# DiyMKbd.net
KiCad netlist of a schematic drawn in EAGLE
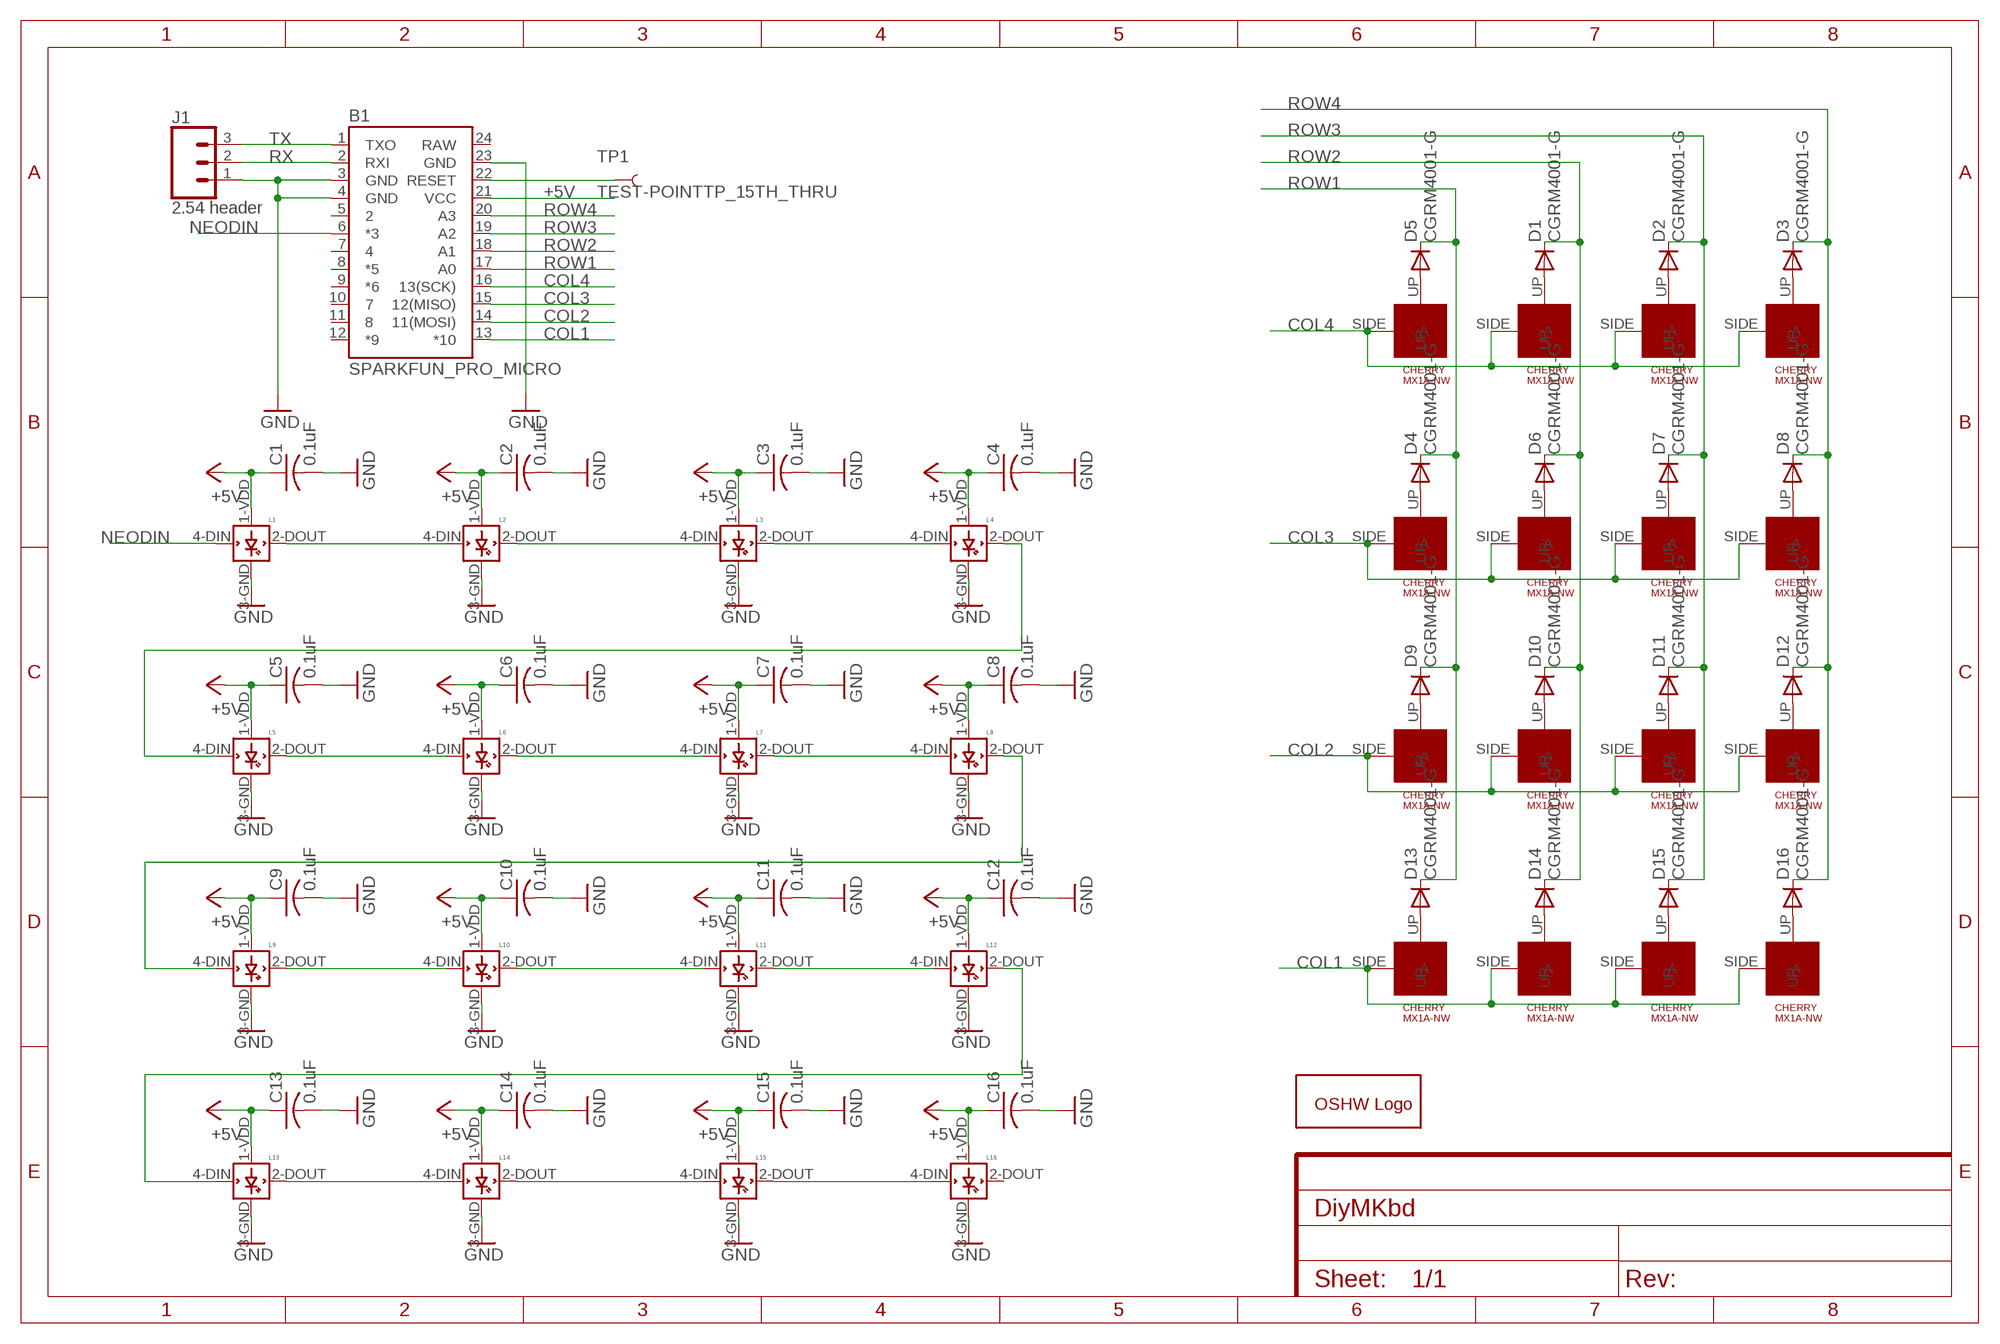
[diagram p0: schematic, sheet 1]

(export (version "E")
  (design (tool "Eeschema 10.0.6"))
  (components
    (comp (ref "B1")
      (value "SPARKFUN_PRO_MICRO")
      (footprint "eagle-import:SPARKFUN_PRO_MICRO")
      (libsource (lib "eagle-import") (part "SPARKFUN_PRO_MICRO"))
    )
    (comp (ref "C1")
      (value "0.1uF")
      (footprint "eagle-import:C0603")
      (libsource (lib "eagle-import") (part "C-USC0603"))
    )
    (comp (ref "C2")
      (value "0.1uF")
      (footprint "eagle-import:C0603")
      (libsource (lib "eagle-import") (part "C-USC0603"))
    )
    (comp (ref "C3")
      (value "0.1uF")
      (footprint "eagle-import:C0603")
      (libsource (lib "eagle-import") (part "C-USC0603"))
    )
    (comp (ref "C4")
      (value "0.1uF")
      (footprint "eagle-import:C0603")
      (libsource (lib "eagle-import") (part "C-USC0603"))
    )
    (comp (ref "C5")
      (value "0.1uF")
      (footprint "eagle-import:C0603")
      (libsource (lib "eagle-import") (part "C-USC0603"))
    )
    (comp (ref "C6")
      (value "0.1uF")
      (footprint "eagle-import:C0603")
      (libsource (lib "eagle-import") (part "C-USC0603"))
    )
    (comp (ref "C7")
      (value "0.1uF")
      (footprint "eagle-import:C0603")
      (libsource (lib "eagle-import") (part "C-USC0603"))
    )
    (comp (ref "C8")
      (value "0.1uF")
      (footprint "eagle-import:C0603")
      (libsource (lib "eagle-import") (part "C-USC0603"))
    )
    (comp (ref "C9")
      (value "0.1uF")
      (footprint "eagle-import:C0603")
      (libsource (lib "eagle-import") (part "C-USC0603"))
    )
    (comp (ref "C10")
      (value "0.1uF")
      (footprint "eagle-import:C0603")
      (libsource (lib "eagle-import") (part "C-USC0603"))
    )
    (comp (ref "C11")
      (value "0.1uF")
      (footprint "eagle-import:C0603")
      (libsource (lib "eagle-import") (part "C-USC0603"))
    )
    (comp (ref "C12")
      (value "0.1uF")
      (footprint "eagle-import:C0603")
      (libsource (lib "eagle-import") (part "C-USC0603"))
    )
    (comp (ref "C13")
      (value "0.1uF")
      (footprint "eagle-import:C0603")
      (libsource (lib "eagle-import") (part "C-USC0603"))
    )
    (comp (ref "C14")
      (value "0.1uF")
      (footprint "eagle-import:C0603")
      (libsource (lib "eagle-import") (part "C-USC0603"))
    )
    (comp (ref "C15")
      (value "0.1uF")
      (footprint "eagle-import:C0603")
      (libsource (lib "eagle-import") (part "C-USC0603"))
    )
    (comp (ref "C16")
      (value "0.1uF")
      (footprint "eagle-import:C0603")
      (libsource (lib "eagle-import") (part "C-USC0603"))
    )
    (comp (ref "D1")
      (value "CGRM4001-G")
      (footprint "eagle-import:SOD-123_MINI-SMA")
      (libsource (lib "eagle-import") (part "CGRM400-G1"))
    )
    (comp (ref "D2")
      (value "CGRM4001-G")
      (footprint "eagle-import:SOD-123_MINI-SMA")
      (libsource (lib "eagle-import") (part "CGRM400-G1"))
    )
    (comp (ref "D3")
      (value "CGRM4001-G")
      (footprint "eagle-import:SOD-123_MINI-SMA")
      (libsource (lib "eagle-import") (part "CGRM400-G1"))
    )
    (comp (ref "D4")
      (value "CGRM4001-G")
      (footprint "eagle-import:SOD-123_MINI-SMA")
      (libsource (lib "eagle-import") (part "CGRM400-G1"))
    )
    (comp (ref "D5")
      (value "CGRM4001-G")
      (footprint "eagle-import:SOD-123_MINI-SMA")
      (libsource (lib "eagle-import") (part "CGRM400-G1"))
    )
    (comp (ref "D6")
      (value "CGRM4001-G")
      (footprint "eagle-import:SOD-123_MINI-SMA")
      (libsource (lib "eagle-import") (part "CGRM400-G1"))
    )
    (comp (ref "D7")
      (value "CGRM4001-G")
      (footprint "eagle-import:SOD-123_MINI-SMA")
      (libsource (lib "eagle-import") (part "CGRM400-G1"))
    )
    (comp (ref "D8")
      (value "CGRM4001-G")
      (footprint "eagle-import:SOD-123_MINI-SMA")
      (libsource (lib "eagle-import") (part "CGRM400-G1"))
    )
    (comp (ref "D9")
      (value "CGRM4001-G")
      (footprint "eagle-import:SOD-123_MINI-SMA")
      (libsource (lib "eagle-import") (part "CGRM400-G1"))
    )
    (comp (ref "D10")
      (value "CGRM4001-G")
      (footprint "eagle-import:SOD-123_MINI-SMA")
      (libsource (lib "eagle-import") (part "CGRM400-G1"))
    )
    (comp (ref "D11")
      (value "CGRM4001-G")
      (footprint "eagle-import:SOD-123_MINI-SMA")
      (libsource (lib "eagle-import") (part "CGRM400-G1"))
    )
    (comp (ref "D12")
      (value "CGRM4001-G")
      (footprint "eagle-import:SOD-123_MINI-SMA")
      (libsource (lib "eagle-import") (part "CGRM400-G1"))
    )
    (comp (ref "D13")
      (value "CGRM4001-G")
      (footprint "eagle-import:SOD-123_MINI-SMA")
      (libsource (lib "eagle-import") (part "CGRM400-G1"))
    )
    (comp (ref "D14")
      (value "CGRM4001-G")
      (footprint "eagle-import:SOD-123_MINI-SMA")
      (libsource (lib "eagle-import") (part "CGRM400-G1"))
    )
    (comp (ref "D15")
      (value "CGRM4001-G")
      (footprint "eagle-import:SOD-123_MINI-SMA")
      (libsource (lib "eagle-import") (part "CGRM400-G1"))
    )
    (comp (ref "D16")
      (value "CGRM4001-G")
      (footprint "eagle-import:SOD-123_MINI-SMA")
      (libsource (lib "eagle-import") (part "CGRM400-G1"))
    )
    (comp (ref "GOLD_ORB_SM1")
      (value "OSHWLOGOLOGO5MM")
      (footprint "eagle-import:OSHW_5MM")
      (libsource (lib "eagle-import") (part "OSHWLOGOLOGO5MM"))
    )
    (comp (ref "J1")
      (value "2.54 header")
      (footprint "eagle-import:1X03_LOCK")
      (libsource (lib "eagle-import") (part "CONN_03LOCK"))
    )
    (comp (ref "L1")
      (value "WS2812B")
      (footprint "eagle-import:WS2812B")
      (libsource (lib "eagle-import") (part "WS2812B"))
    )
    (comp (ref "L2")
      (value "WS2812B")
      (footprint "eagle-import:WS2812B")
      (libsource (lib "eagle-import") (part "WS2812B"))
    )
    (comp (ref "L3")
      (value "WS2812B")
      (footprint "eagle-import:WS2812B")
      (libsource (lib "eagle-import") (part "WS2812B"))
    )
    (comp (ref "L4")
      (value "WS2812B")
      (footprint "eagle-import:WS2812B")
      (libsource (lib "eagle-import") (part "WS2812B"))
    )
    (comp (ref "L5")
      (value "WS2812B")
      (footprint "eagle-import:WS2812B")
      (libsource (lib "eagle-import") (part "WS2812B"))
    )
    (comp (ref "L6")
      (value "WS2812B")
      (footprint "eagle-import:WS2812B")
      (libsource (lib "eagle-import") (part "WS2812B"))
    )
    (comp (ref "L7")
      (value "WS2812B")
      (footprint "eagle-import:WS2812B")
      (libsource (lib "eagle-import") (part "WS2812B"))
    )
    (comp (ref "L8")
      (value "WS2812B")
      (footprint "eagle-import:WS2812B")
      (libsource (lib "eagle-import") (part "WS2812B"))
    )
    (comp (ref "L9")
      (value "WS2812B")
      (footprint "eagle-import:WS2812B")
      (libsource (lib "eagle-import") (part "WS2812B"))
    )
    (comp (ref "L10")
      (value "WS2812B")
      (footprint "eagle-import:WS2812B")
      (libsource (lib "eagle-import") (part "WS2812B"))
    )
    (comp (ref "L11")
      (value "WS2812B")
      (footprint "eagle-import:WS2812B")
      (libsource (lib "eagle-import") (part "WS2812B"))
    )
    (comp (ref "L12")
      (value "WS2812B")
      (footprint "eagle-import:WS2812B")
      (libsource (lib "eagle-import") (part "WS2812B"))
    )
    (comp (ref "L13")
      (value "WS2812B")
      (footprint "eagle-import:WS2812B")
      (libsource (lib "eagle-import") (part "WS2812B"))
    )
    (comp (ref "L14")
      (value "WS2812B")
      (footprint "eagle-import:WS2812B")
      (libsource (lib "eagle-import") (part "WS2812B"))
    )
    (comp (ref "L15")
      (value "WS2812B")
      (footprint "eagle-import:WS2812B")
      (libsource (lib "eagle-import") (part "WS2812B"))
    )
    (comp (ref "L16")
      (value "WS2812B")
      (footprint "eagle-import:WS2812B")
      (libsource (lib "eagle-import") (part "WS2812B"))
    )
    (comp (ref "TP1")
      (value "TEST-POINTTP_15TH_THRU")
      (footprint "eagle-import:TP_15TH")
      (libsource (lib "eagle-import") (part "TEST-POINTTP_15TH_THRU"))
    )
    (comp (ref "U$1")
      (value "CHERRY-MX1A-E1NW")
      (footprint "eagle-import:CHERRYMX-NN")
      (libsource (lib "eagle-import") (part "CHERRY-MX1A-E1NW"))
    )
    (comp (ref "U$2")
      (value "CHERRY-MX1A-E1NW")
      (footprint "eagle-import:CHERRYMX-NN")
      (libsource (lib "eagle-import") (part "CHERRY-MX1A-E1NW"))
    )
    (comp (ref "U$3")
      (value "CHERRY-MX1A-E1NW")
      (footprint "eagle-import:CHERRYMX-NN")
      (libsource (lib "eagle-import") (part "CHERRY-MX1A-E1NW"))
    )
    (comp (ref "U$4")
      (value "CHERRY-MX1A-E1NW")
      (footprint "eagle-import:CHERRYMX-NN")
      (libsource (lib "eagle-import") (part "CHERRY-MX1A-E1NW"))
    )
    (comp (ref "U$7")
      (value "CHERRY-MX1A-E1NW")
      (footprint "eagle-import:CHERRYMX-NN")
      (libsource (lib "eagle-import") (part "CHERRY-MX1A-E1NW"))
    )
    (comp (ref "U$8")
      (value "CHERRY-MX1A-E1NW")
      (footprint "eagle-import:CHERRYMX-NN")
      (libsource (lib "eagle-import") (part "CHERRY-MX1A-E1NW"))
    )
    (comp (ref "U$9")
      (value "CHERRY-MX1A-E1NW")
      (footprint "eagle-import:CHERRYMX-NN")
      (libsource (lib "eagle-import") (part "CHERRY-MX1A-E1NW"))
    )
    (comp (ref "U$10")
      (value "CHERRY-MX1A-E1NW")
      (footprint "eagle-import:CHERRYMX-NN")
      (libsource (lib "eagle-import") (part "CHERRY-MX1A-E1NW"))
    )
    (comp (ref "U$19")
      (value "CHERRY-MX1A-E1NW")
      (footprint "eagle-import:CHERRYMX-NN")
      (libsource (lib "eagle-import") (part "CHERRY-MX1A-E1NW"))
    )
    (comp (ref "U$20")
      (value "CHERRY-MX1A-E1NW")
      (footprint "eagle-import:CHERRYMX-NN")
      (libsource (lib "eagle-import") (part "CHERRY-MX1A-E1NW"))
    )
    (comp (ref "U$21")
      (value "CHERRY-MX1A-E1NW")
      (footprint "eagle-import:CHERRYMX-NN")
      (libsource (lib "eagle-import") (part "CHERRY-MX1A-E1NW"))
    )
    (comp (ref "U$22")
      (value "CHERRY-MX1A-E1NW")
      (footprint "eagle-import:CHERRYMX-NN")
      (libsource (lib "eagle-import") (part "CHERRY-MX1A-E1NW"))
    )
    (comp (ref "U$25")
      (value "CHERRY-MX1A-E1NW")
      (footprint "eagle-import:CHERRYMX-NN")
      (libsource (lib "eagle-import") (part "CHERRY-MX1A-E1NW"))
    )
    (comp (ref "U$26")
      (value "CHERRY-MX1A-E1NW")
      (footprint "eagle-import:CHERRYMX-NN")
      (libsource (lib "eagle-import") (part "CHERRY-MX1A-E1NW"))
    )
    (comp (ref "U$27")
      (value "CHERRY-MX1A-E1NW")
      (footprint "eagle-import:CHERRYMX-NN")
      (libsource (lib "eagle-import") (part "CHERRY-MX1A-E1NW"))
    )
    (comp (ref "U$28")
      (value "CHERRY-MX1A-E1NW")
      (footprint "eagle-import:CHERRYMX-NN")
      (libsource (lib "eagle-import") (part "CHERRY-MX1A-E1NW"))
    )
  )
  (nets
    (net (code "1") (name "+5V") (class "Default")
      (node (ref "B1") (pin "21") (pinfunction "VCC_21") (pintype "power_in"))
      (node (ref "C1") (pin "1") (pinfunction "1_1") (pintype "passive"))
      (node (ref "C10") (pin "1") (pinfunction "1_1") (pintype "passive"))
      (node (ref "C11") (pin "1") (pinfunction "1_1") (pintype "passive"))
      (node (ref "C12") (pin "1") (pinfunction "1_1") (pintype "passive"))
      (node (ref "C13") (pin "1") (pinfunction "1_1") (pintype "passive"))
      (node (ref "C14") (pin "1") (pinfunction "1_1") (pintype "passive"))
      (node (ref "C15") (pin "1") (pinfunction "1_1") (pintype "passive"))
      (node (ref "C16") (pin "1") (pinfunction "1_1") (pintype "passive"))
      (node (ref "C2") (pin "1") (pinfunction "1_1") (pintype "passive"))
      (node (ref "C3") (pin "1") (pinfunction "1_1") (pintype "passive"))
      (node (ref "C4") (pin "1") (pinfunction "1_1") (pintype "passive"))
      (node (ref "C5") (pin "1") (pinfunction "1_1") (pintype "passive"))
      (node (ref "C6") (pin "1") (pinfunction "1_1") (pintype "passive"))
      (node (ref "C7") (pin "1") (pinfunction "1_1") (pintype "passive"))
      (node (ref "C8") (pin "1") (pinfunction "1_1") (pintype "passive"))
      (node (ref "C9") (pin "1") (pinfunction "1_1") (pintype "passive"))
      (node (ref "L1") (pin "1-VDD") (pinfunction "VDD_1-VDD") (pintype "bidirectional"))
      (node (ref "L10") (pin "1-VDD") (pinfunction "VDD_1-VDD") (pintype "bidirectional"))
      (node (ref "L11") (pin "1-VDD") (pinfunction "VDD_1-VDD") (pintype "bidirectional"))
      (node (ref "L12") (pin "1-VDD") (pinfunction "VDD_1-VDD") (pintype "bidirectional"))
      (node (ref "L13") (pin "1-VDD") (pinfunction "VDD_1-VDD") (pintype "bidirectional"))
      (node (ref "L14") (pin "1-VDD") (pinfunction "VDD_1-VDD") (pintype "bidirectional"))
      (node (ref "L15") (pin "1-VDD") (pinfunction "VDD_1-VDD") (pintype "bidirectional"))
      (node (ref "L16") (pin "1-VDD") (pinfunction "VDD_1-VDD") (pintype "bidirectional"))
      (node (ref "L2") (pin "1-VDD") (pinfunction "VDD_1-VDD") (pintype "bidirectional"))
      (node (ref "L3") (pin "1-VDD") (pinfunction "VDD_1-VDD") (pintype "bidirectional"))
      (node (ref "L4") (pin "1-VDD") (pinfunction "VDD_1-VDD") (pintype "bidirectional"))
      (node (ref "L5") (pin "1-VDD") (pinfunction "VDD_1-VDD") (pintype "bidirectional"))
      (node (ref "L6") (pin "1-VDD") (pinfunction "VDD_1-VDD") (pintype "bidirectional"))
      (node (ref "L7") (pin "1-VDD") (pinfunction "VDD_1-VDD") (pintype "bidirectional"))
      (node (ref "L8") (pin "1-VDD") (pinfunction "VDD_1-VDD") (pintype "bidirectional"))
      (node (ref "L9") (pin "1-VDD") (pinfunction "VDD_1-VDD") (pintype "bidirectional"))
    )
    (net (code "2") (name "/COL1") (class "Default")
      (node (ref "B1") (pin "13") (pinfunction "*10_13") (pintype "bidirectional"))
      (node (ref "U$25") (pin "SIDE") (pinfunction "A_SIDE") (pintype "bidirectional"))
      (node (ref "U$26") (pin "SIDE") (pinfunction "A_SIDE") (pintype "bidirectional"))
      (node (ref "U$27") (pin "SIDE") (pinfunction "A_SIDE") (pintype "bidirectional"))
      (node (ref "U$28") (pin "SIDE") (pinfunction "A_SIDE") (pintype "bidirectional"))
    )
    (net (code "3") (name "/COL2") (class "Default")
      (node (ref "B1") (pin "14") (pinfunction "11(MOSI)_14") (pintype "bidirectional"))
      (node (ref "U$10") (pin "SIDE") (pinfunction "A_SIDE") (pintype "bidirectional"))
      (node (ref "U$7") (pin "SIDE") (pinfunction "A_SIDE") (pintype "bidirectional"))
      (node (ref "U$8") (pin "SIDE") (pinfunction "A_SIDE") (pintype "bidirectional"))
      (node (ref "U$9") (pin "SIDE") (pinfunction "A_SIDE") (pintype "bidirectional"))
    )
    (net (code "4") (name "/COL3") (class "Default")
      (node (ref "B1") (pin "15") (pinfunction "12(MISO)_15") (pintype "bidirectional"))
      (node (ref "U$1") (pin "SIDE") (pinfunction "A_SIDE") (pintype "bidirectional"))
      (node (ref "U$2") (pin "SIDE") (pinfunction "A_SIDE") (pintype "bidirectional"))
      (node (ref "U$3") (pin "SIDE") (pinfunction "A_SIDE") (pintype "bidirectional"))
      (node (ref "U$4") (pin "SIDE") (pinfunction "A_SIDE") (pintype "bidirectional"))
    )
    (net (code "5") (name "/COL4") (class "Default")
      (node (ref "B1") (pin "16") (pinfunction "13(SCK)_16") (pintype "bidirectional"))
      (node (ref "U$19") (pin "SIDE") (pinfunction "A_SIDE") (pintype "bidirectional"))
      (node (ref "U$20") (pin "SIDE") (pinfunction "A_SIDE") (pintype "bidirectional"))
      (node (ref "U$21") (pin "SIDE") (pinfunction "A_SIDE") (pintype "bidirectional"))
      (node (ref "U$22") (pin "SIDE") (pinfunction "A_SIDE") (pintype "bidirectional"))
    )
    (net (code "6") (name "/NEODIN") (class "Default")
      (node (ref "B1") (pin "6") (pinfunction "*3_6") (pintype "bidirectional"))
      (node (ref "L1") (pin "4-DIN") (pinfunction "DIN_4-DIN") (pintype "input"))
    )
    (net (code "7") (name "/RAW") (class "Default")
      (node (ref "B1") (pin "24") (pinfunction "RAW_24") (pintype "power_in"))
    )
    (net (code "8") (name "/ROW1") (class "Default")
      (node (ref "B1") (pin "17") (pinfunction "A0_17") (pintype "bidirectional"))
      (node (ref "D13") (pin "C") (pinfunction "C_C") (pintype "passive"))
      (node (ref "D4") (pin "C") (pinfunction "C_C") (pintype "passive"))
      (node (ref "D5") (pin "C") (pinfunction "C_C") (pintype "passive"))
      (node (ref "D9") (pin "C") (pinfunction "C_C") (pintype "passive"))
    )
    (net (code "9") (name "/ROW2") (class "Default")
      (node (ref "B1") (pin "18") (pinfunction "A1_18") (pintype "bidirectional"))
      (node (ref "D1") (pin "C") (pinfunction "C_C") (pintype "passive"))
      (node (ref "D10") (pin "C") (pinfunction "C_C") (pintype "passive"))
      (node (ref "D14") (pin "C") (pinfunction "C_C") (pintype "passive"))
      (node (ref "D6") (pin "C") (pinfunction "C_C") (pintype "passive"))
    )
    (net (code "10") (name "/ROW3") (class "Default")
      (node (ref "B1") (pin "19") (pinfunction "A2_19") (pintype "bidirectional"))
      (node (ref "D11") (pin "C") (pinfunction "C_C") (pintype "passive"))
      (node (ref "D15") (pin "C") (pinfunction "C_C") (pintype "passive"))
      (node (ref "D2") (pin "C") (pinfunction "C_C") (pintype "passive"))
      (node (ref "D7") (pin "C") (pinfunction "C_C") (pintype "passive"))
    )
    (net (code "11") (name "/ROW4") (class "Default")
      (node (ref "B1") (pin "20") (pinfunction "A3_20") (pintype "bidirectional"))
      (node (ref "D12") (pin "C") (pinfunction "C_C") (pintype "passive"))
      (node (ref "D16") (pin "C") (pinfunction "C_C") (pintype "passive"))
      (node (ref "D3") (pin "C") (pinfunction "C_C") (pintype "passive"))
      (node (ref "D8") (pin "C") (pinfunction "C_C") (pintype "passive"))
    )
    (net (code "12") (name "/RX") (class "Default")
      (node (ref "B1") (pin "2") (pinfunction "RXI_2") (pintype "bidirectional"))
      (node (ref "J1") (pin "2") (pinfunction "2_2") (pintype "passive"))
    )
    (net (code "13") (name "/TX") (class "Default")
      (node (ref "B1") (pin "1") (pinfunction "TXO_1") (pintype "bidirectional"))
      (node (ref "J1") (pin "3") (pinfunction "3_3") (pintype "passive"))
    )
    (net (code "14") (name "GND") (class "Default")
      (node (ref "B1") (pin "23") (pinfunction "GND_23") (pintype "power_in"))
      (node (ref "B1") (pin "3") (pinfunction "GND_3") (pintype "power_in"))
      (node (ref "B1") (pin "4") (pinfunction "GND_4") (pintype "power_in"))
      (node (ref "C1") (pin "2") (pinfunction "2_2") (pintype "passive"))
      (node (ref "C10") (pin "2") (pinfunction "2_2") (pintype "passive"))
      (node (ref "C11") (pin "2") (pinfunction "2_2") (pintype "passive"))
      (node (ref "C12") (pin "2") (pinfunction "2_2") (pintype "passive"))
      (node (ref "C13") (pin "2") (pinfunction "2_2") (pintype "passive"))
      (node (ref "C14") (pin "2") (pinfunction "2_2") (pintype "passive"))
      (node (ref "C15") (pin "2") (pinfunction "2_2") (pintype "passive"))
      (node (ref "C16") (pin "2") (pinfunction "2_2") (pintype "passive"))
      (node (ref "C2") (pin "2") (pinfunction "2_2") (pintype "passive"))
      (node (ref "C3") (pin "2") (pinfunction "2_2") (pintype "passive"))
      (node (ref "C4") (pin "2") (pinfunction "2_2") (pintype "passive"))
      (node (ref "C5") (pin "2") (pinfunction "2_2") (pintype "passive"))
      (node (ref "C6") (pin "2") (pinfunction "2_2") (pintype "passive"))
      (node (ref "C7") (pin "2") (pinfunction "2_2") (pintype "passive"))
      (node (ref "C8") (pin "2") (pinfunction "2_2") (pintype "passive"))
      (node (ref "C9") (pin "2") (pinfunction "2_2") (pintype "passive"))
      (node (ref "J1") (pin "1") (pinfunction "1_1") (pintype "passive"))
      (node (ref "L1") (pin "3-GND") (pinfunction "GND_3-GND") (pintype "bidirectional"))
      (node (ref "L10") (pin "3-GND") (pinfunction "GND_3-GND") (pintype "bidirectional"))
      (node (ref "L11") (pin "3-GND") (pinfunction "GND_3-GND") (pintype "bidirectional"))
      (node (ref "L12") (pin "3-GND") (pinfunction "GND_3-GND") (pintype "bidirectional"))
      (node (ref "L13") (pin "3-GND") (pinfunction "GND_3-GND") (pintype "bidirectional"))
      (node (ref "L14") (pin "3-GND") (pinfunction "GND_3-GND") (pintype "bidirectional"))
      (node (ref "L15") (pin "3-GND") (pinfunction "GND_3-GND") (pintype "bidirectional"))
      (node (ref "L16") (pin "3-GND") (pinfunction "GND_3-GND") (pintype "bidirectional"))
      (node (ref "L2") (pin "3-GND") (pinfunction "GND_3-GND") (pintype "bidirectional"))
      (node (ref "L3") (pin "3-GND") (pinfunction "GND_3-GND") (pintype "bidirectional"))
      (node (ref "L4") (pin "3-GND") (pinfunction "GND_3-GND") (pintype "bidirectional"))
      (node (ref "L5") (pin "3-GND") (pinfunction "GND_3-GND") (pintype "bidirectional"))
      (node (ref "L6") (pin "3-GND") (pinfunction "GND_3-GND") (pintype "bidirectional"))
      (node (ref "L7") (pin "3-GND") (pinfunction "GND_3-GND") (pintype "bidirectional"))
      (node (ref "L8") (pin "3-GND") (pinfunction "GND_3-GND") (pintype "bidirectional"))
      (node (ref "L9") (pin "3-GND") (pinfunction "GND_3-GND") (pintype "bidirectional"))
    )
    (net (code "15") (name "Net-(B1-RESET)") (class "Default")
      (node (ref "B1") (pin "22") (pinfunction "RESET_22") (pintype "bidirectional"))
      (node (ref "TP1") (pin "P$1") (pinfunction "1_P$1") (pintype "bidirectional"))
    )
    (net (code "16") (name "Net-(D1-PadA)") (class "Default")
      (node (ref "D1") (pin "A") (pinfunction "A_A") (pintype "passive"))
      (node (ref "U$20") (pin "UP") (pinfunction "UP_UP") (pintype "bidirectional"))
    )
    (net (code "17") (name "Net-(D2-PadA)") (class "Default")
      (node (ref "D2") (pin "A") (pinfunction "A_A") (pintype "passive"))
      (node (ref "U$21") (pin "UP") (pinfunction "UP_UP") (pintype "bidirectional"))
    )
    (net (code "18") (name "Net-(D3-PadA)") (class "Default")
      (node (ref "D3") (pin "A") (pinfunction "A_A") (pintype "passive"))
      (node (ref "U$22") (pin "UP") (pinfunction "UP_UP") (pintype "bidirectional"))
    )
    (net (code "19") (name "Net-(D4-PadA)") (class "Default")
      (node (ref "D4") (pin "A") (pinfunction "A_A") (pintype "passive"))
      (node (ref "U$2") (pin "UP") (pinfunction "UP_UP") (pintype "bidirectional"))
    )
    (net (code "20") (name "Net-(D5-PadA)") (class "Default")
      (node (ref "D5") (pin "A") (pinfunction "A_A") (pintype "passive"))
      (node (ref "U$19") (pin "UP") (pinfunction "UP_UP") (pintype "bidirectional"))
    )
    (net (code "21") (name "Net-(D6-PadA)") (class "Default")
      (node (ref "D6") (pin "A") (pinfunction "A_A") (pintype "passive"))
      (node (ref "U$1") (pin "UP") (pinfunction "UP_UP") (pintype "bidirectional"))
    )
    (net (code "22") (name "Net-(D7-PadA)") (class "Default")
      (node (ref "D7") (pin "A") (pinfunction "A_A") (pintype "passive"))
      (node (ref "U$3") (pin "UP") (pinfunction "UP_UP") (pintype "bidirectional"))
    )
    (net (code "23") (name "Net-(D8-PadA)") (class "Default")
      (node (ref "D8") (pin "A") (pinfunction "A_A") (pintype "passive"))
      (node (ref "U$4") (pin "UP") (pinfunction "UP_UP") (pintype "bidirectional"))
    )
    (net (code "24") (name "Net-(D9-PadA)") (class "Default")
      (node (ref "D9") (pin "A") (pinfunction "A_A") (pintype "passive"))
      (node (ref "U$7") (pin "UP") (pinfunction "UP_UP") (pintype "bidirectional"))
    )
    (net (code "25") (name "Net-(D10-PadA)") (class "Default")
      (node (ref "D10") (pin "A") (pinfunction "A_A") (pintype "passive"))
      (node (ref "U$8") (pin "UP") (pinfunction "UP_UP") (pintype "bidirectional"))
    )
    (net (code "26") (name "Net-(D11-PadA)") (class "Default")
      (node (ref "D11") (pin "A") (pinfunction "A_A") (pintype "passive"))
      (node (ref "U$9") (pin "UP") (pinfunction "UP_UP") (pintype "bidirectional"))
    )
    (net (code "27") (name "Net-(D12-PadA)") (class "Default")
      (node (ref "D12") (pin "A") (pinfunction "A_A") (pintype "passive"))
      (node (ref "U$10") (pin "UP") (pinfunction "UP_UP") (pintype "bidirectional"))
    )
    (net (code "28") (name "Net-(D13-PadA)") (class "Default")
      (node (ref "D13") (pin "A") (pinfunction "A_A") (pintype "passive"))
      (node (ref "U$25") (pin "UP") (pinfunction "UP_UP") (pintype "bidirectional"))
    )
    (net (code "29") (name "Net-(D14-PadA)") (class "Default")
      (node (ref "D14") (pin "A") (pinfunction "A_A") (pintype "passive"))
      (node (ref "U$26") (pin "UP") (pinfunction "UP_UP") (pintype "bidirectional"))
    )
    (net (code "30") (name "Net-(D15-PadA)") (class "Default")
      (node (ref "D15") (pin "A") (pinfunction "A_A") (pintype "passive"))
      (node (ref "U$27") (pin "UP") (pinfunction "UP_UP") (pintype "bidirectional"))
    )
    (net (code "31") (name "Net-(D16-PadA)") (class "Default")
      (node (ref "D16") (pin "A") (pinfunction "A_A") (pintype "passive"))
      (node (ref "U$28") (pin "UP") (pinfunction "UP_UP") (pintype "bidirectional"))
    )
    (net (code "32") (name "Net-(L1-DOUT)") (class "Default")
      (node (ref "L1") (pin "2-DOUT") (pinfunction "DOUT_2-DOUT") (pintype "output"))
      (node (ref "L2") (pin "4-DIN") (pinfunction "DIN_4-DIN") (pintype "input"))
    )
    (net (code "33") (name "Net-(L2-DOUT)") (class "Default")
      (node (ref "L2") (pin "2-DOUT") (pinfunction "DOUT_2-DOUT") (pintype "output"))
      (node (ref "L3") (pin "4-DIN") (pinfunction "DIN_4-DIN") (pintype "input"))
    )
    (net (code "34") (name "Net-(L3-DOUT)") (class "Default")
      (node (ref "L3") (pin "2-DOUT") (pinfunction "DOUT_2-DOUT") (pintype "output"))
      (node (ref "L4") (pin "4-DIN") (pinfunction "DIN_4-DIN") (pintype "input"))
    )
    (net (code "35") (name "Net-(L4-DOUT)") (class "Default")
      (node (ref "L4") (pin "2-DOUT") (pinfunction "DOUT_2-DOUT") (pintype "output"))
      (node (ref "L5") (pin "4-DIN") (pinfunction "DIN_4-DIN") (pintype "input"))
    )
    (net (code "36") (name "Net-(L5-DOUT)") (class "Default")
      (node (ref "L5") (pin "2-DOUT") (pinfunction "DOUT_2-DOUT") (pintype "output"))
      (node (ref "L6") (pin "4-DIN") (pinfunction "DIN_4-DIN") (pintype "input"))
    )
    (net (code "37") (name "Net-(L6-DOUT)") (class "Default")
      (node (ref "L6") (pin "2-DOUT") (pinfunction "DOUT_2-DOUT") (pintype "output"))
      (node (ref "L7") (pin "4-DIN") (pinfunction "DIN_4-DIN") (pintype "input"))
    )
    (net (code "38") (name "Net-(L7-DOUT)") (class "Default")
      (node (ref "L7") (pin "2-DOUT") (pinfunction "DOUT_2-DOUT") (pintype "output"))
      (node (ref "L8") (pin "4-DIN") (pinfunction "DIN_4-DIN") (pintype "input"))
    )
    (net (code "39") (name "Net-(L8-DOUT)") (class "Default")
      (node (ref "L8") (pin "2-DOUT") (pinfunction "DOUT_2-DOUT") (pintype "output"))
      (node (ref "L9") (pin "4-DIN") (pinfunction "DIN_4-DIN") (pintype "input"))
    )
    (net (code "40") (name "Net-(L10-DIN)") (class "Default")
      (node (ref "L10") (pin "4-DIN") (pinfunction "DIN_4-DIN") (pintype "input"))
      (node (ref "L9") (pin "2-DOUT") (pinfunction "DOUT_2-DOUT") (pintype "output"))
    )
    (net (code "41") (name "Net-(L10-DOUT)") (class "Default")
      (node (ref "L10") (pin "2-DOUT") (pinfunction "DOUT_2-DOUT") (pintype "output"))
      (node (ref "L11") (pin "4-DIN") (pinfunction "DIN_4-DIN") (pintype "input"))
    )
    (net (code "42") (name "Net-(L11-DOUT)") (class "Default")
      (node (ref "L11") (pin "2-DOUT") (pinfunction "DOUT_2-DOUT") (pintype "output"))
      (node (ref "L12") (pin "4-DIN") (pinfunction "DIN_4-DIN") (pintype "input"))
    )
    (net (code "43") (name "Net-(L12-DOUT)") (class "Default")
      (node (ref "L12") (pin "2-DOUT") (pinfunction "DOUT_2-DOUT") (pintype "output"))
      (node (ref "L13") (pin "4-DIN") (pinfunction "DIN_4-DIN") (pintype "input"))
    )
    (net (code "44") (name "Net-(L13-DOUT)") (class "Default")
      (node (ref "L13") (pin "2-DOUT") (pinfunction "DOUT_2-DOUT") (pintype "output"))
      (node (ref "L14") (pin "4-DIN") (pinfunction "DIN_4-DIN") (pintype "input"))
    )
    (net (code "45") (name "Net-(L14-DOUT)") (class "Default")
      (node (ref "L14") (pin "2-DOUT") (pinfunction "DOUT_2-DOUT") (pintype "output"))
      (node (ref "L15") (pin "4-DIN") (pinfunction "DIN_4-DIN") (pintype "input"))
    )
    (net (code "46") (name "Net-(L15-DOUT)") (class "Default")
      (node (ref "L15") (pin "2-DOUT") (pinfunction "DOUT_2-DOUT") (pintype "output"))
      (node (ref "L16") (pin "4-DIN") (pinfunction "DIN_4-DIN") (pintype "input"))
    )
    (net (code "47") (name "unconnected-(B1-*5-Pad8)") (class "Default")
      (node (ref "B1") (pin "8") (pinfunction "*5_8") (pintype "bidirectional"))
    )
    (net (code "48") (name "unconnected-(B1-*6-Pad9)") (class "Default")
      (node (ref "B1") (pin "9") (pinfunction "*6_9") (pintype "bidirectional"))
    )
    (net (code "49") (name "unconnected-(B1-*9-Pad12)") (class "Default")
      (node (ref "B1") (pin "12") (pinfunction "*9_12") (pintype "bidirectional"))
    )
    (net (code "50") (name "unconnected-(B1-2-Pad5)") (class "Default")
      (node (ref "B1") (pin "5") (pinfunction "2_5") (pintype "bidirectional"))
    )
    (net (code "51") (name "unconnected-(B1-4-Pad7)") (class "Default")
      (node (ref "B1") (pin "7") (pinfunction "4_7") (pintype "bidirectional"))
    )
    (net (code "52") (name "unconnected-(B1-7-Pad10)") (class "Default")
      (node (ref "B1") (pin "10") (pinfunction "7_10") (pintype "bidirectional"))
    )
    (net (code "53") (name "unconnected-(B1-8-Pad11)") (class "Default")
      (node (ref "B1") (pin "11") (pinfunction "8_11") (pintype "bidirectional"))
    )
    (net (code "54") (name "unconnected-(L16-DOUT-Pad2-DOUT)") (class "Default")
      (node (ref "L16") (pin "2-DOUT") (pinfunction "DOUT_2-DOUT") (pintype "output"))
    )
  )
)
